# 7_ETH.net
KiCad netlist of a schematic drawn in Altium Designer
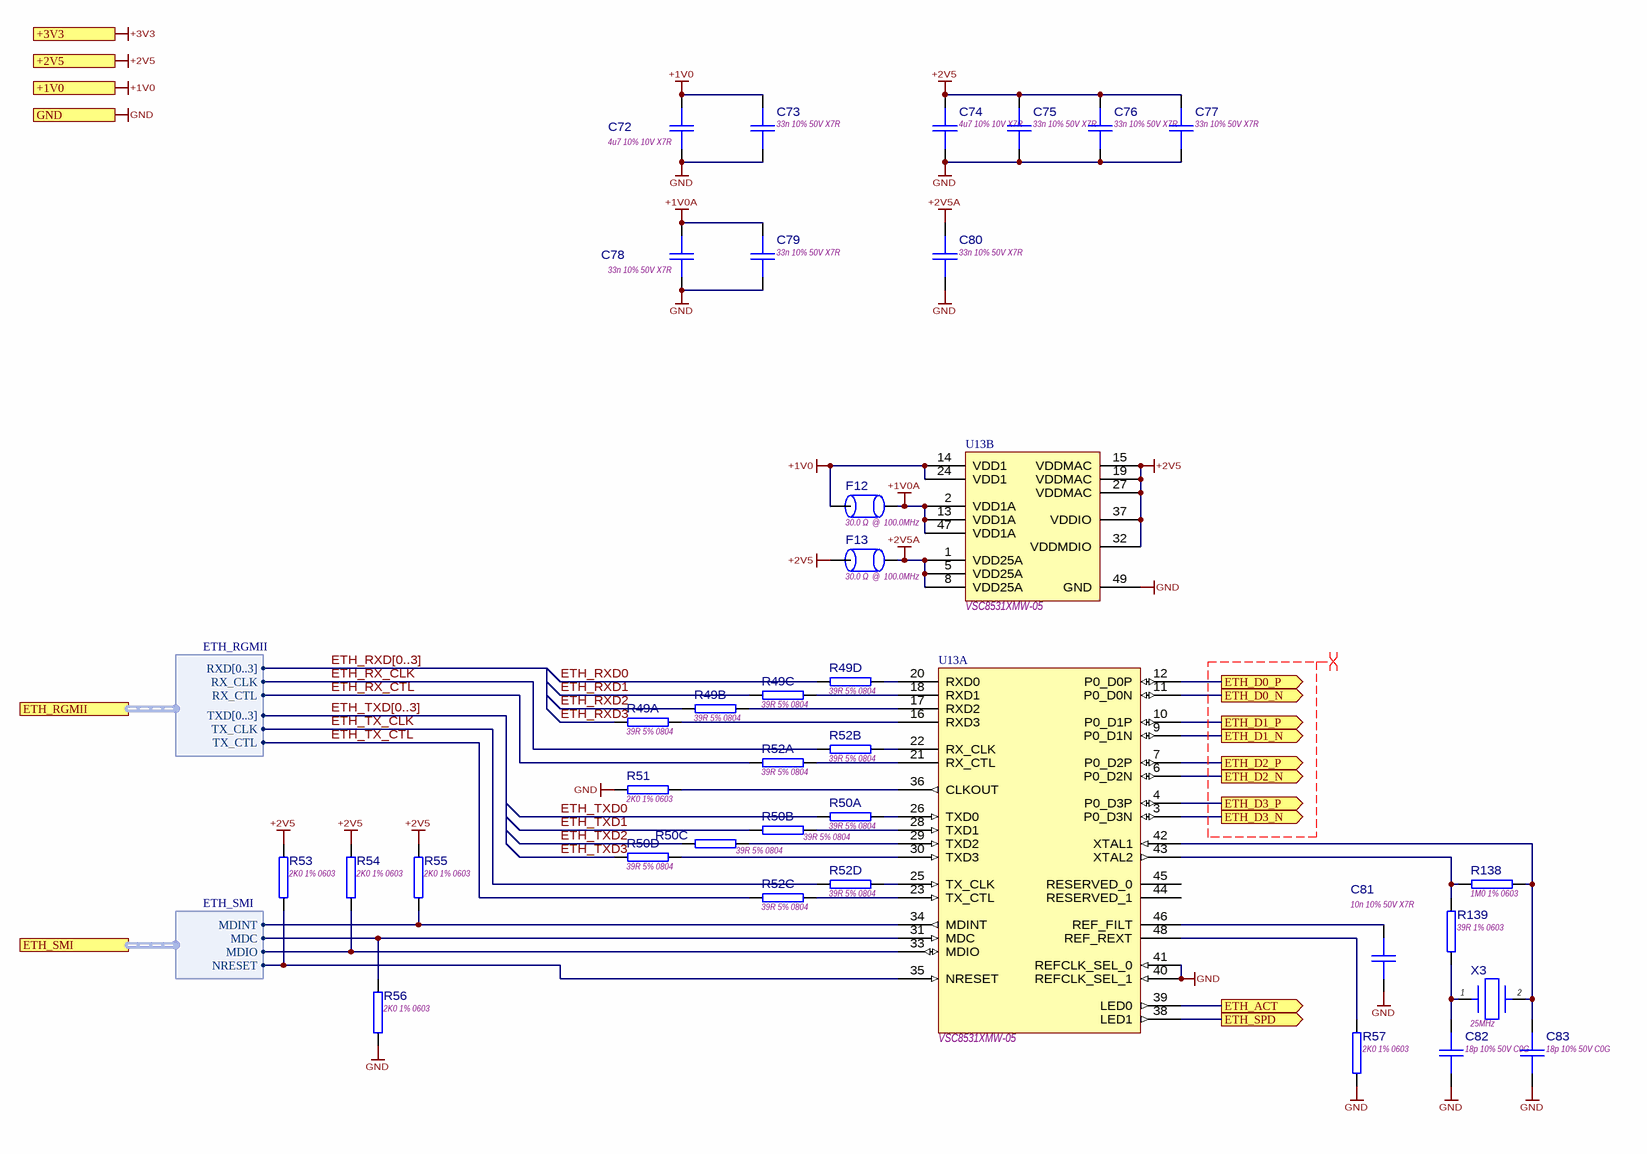
[diagram p0: [7] ETH.SchDoc]

(export (version "E")
  (design (tool "Eeschema 10.0.6"))
  (components
    (comp (ref "C72")
      (value "4u7 10% 10V X7R")
      (footprint "CAPC2012X145N")
      (description "Ceramic Chip Capacitor, 0805/2012")
      (fields (field (name "TOLERANCE") "10%"))
      (libsource (lib "Omnisys Vault") (part "CAP-2PIN"))
    )
    (comp (ref "C73")
      (value "33n 10% 50V X7R")
      (footprint "CAPC1005X55N")
      (description "Ceramic Chip Capacitor, 0402/1005")
      (fields (field (name "TOLERANCE") "10%"))
      (libsource (lib "Omnisys Vault") (part "CAP-2PIN"))
    )
    (comp (ref "C74")
      (value "4u7 10% 10V X7R")
      (footprint "CAPC2012X145N")
      (description "Ceramic Chip Capacitor, 0805/2012")
      (fields (field (name "TOLERANCE") "10%"))
      (libsource (lib "Omnisys Vault") (part "CAP-2PIN"))
    )
    (comp (ref "C75")
      (value "33n 10% 50V X7R")
      (footprint "CAPC1005X55N")
      (description "Ceramic Chip Capacitor, 0402/1005")
      (fields (field (name "TOLERANCE") "10%"))
      (libsource (lib "Omnisys Vault") (part "CAP-2PIN"))
    )
    (comp (ref "C76")
      (value "33n 10% 50V X7R")
      (footprint "CAPC1005X55N")
      (description "Ceramic Chip Capacitor, 0402/1005")
      (fields (field (name "TOLERANCE") "10%"))
      (libsource (lib "Omnisys Vault") (part "CAP-2PIN"))
    )
    (comp (ref "C77")
      (value "33n 10% 50V X7R")
      (footprint "CAPC1005X55N")
      (description "Ceramic Chip Capacitor, 0402/1005")
      (fields (field (name "TOLERANCE") "10%"))
      (libsource (lib "Omnisys Vault") (part "CAP-2PIN"))
    )
    (comp (ref "C78")
      (value "33n 10% 50V X7R")
      (footprint "CAPC1005X55N")
      (description "Ceramic Chip Capacitor, 0402/1005")
      (fields (field (name "TOLERANCE") "10%"))
      (libsource (lib "Omnisys Vault") (part "CAP-2PIN"))
    )
    (comp (ref "C79")
      (value "33n 10% 50V X7R")
      (footprint "CAPC1005X55N")
      (description "Ceramic Chip Capacitor, 0402/1005")
      (fields (field (name "TOLERANCE") "10%"))
      (libsource (lib "Omnisys Vault") (part "CAP-2PIN"))
    )
    (comp (ref "C80")
      (value "33n 10% 50V X7R")
      (footprint "CAPC1005X55N")
      (description "Ceramic Chip Capacitor, 0402/1005")
      (fields (field (name "TOLERANCE") "10%"))
      (libsource (lib "Omnisys Vault") (part "CAP-2PIN"))
    )
    (comp (ref "C81")
      (value "10n 10% 50V X7R")
      (footprint "CAPC1608X90N")
      (description "Ceramic Chip Capacitor, 0603/1608")
      (fields (field (name "TOLERANCE") "5%"))
      (libsource (lib "Omnisys Vault") (part "CAP-2PIN"))
    )
    (comp (ref "C82")
      (value "18p 10% 50V C0G")
      (footprint "CAPC1608X90N")
      (description "Ceramic Chip Capacitor, 0603/1608")
      (fields (field (name "TOLERANCE") "5%"))
      (libsource (lib "Omnisys Vault") (part "CAP-2PIN"))
    )
    (comp (ref "C83")
      (value "18p 10% 50V C0G")
      (footprint "CAPC1608X90N")
      (description "Ceramic Chip Capacitor, 0603/1608")
      (fields (field (name "TOLERANCE") "5%"))
      (libsource (lib "Omnisys Vault") (part "CAP-2PIN"))
    )
    (comp (ref "F12")
      (value "30.0 Ω  @  100.0MHz")
      (footprint "INDC2012X11L")
      (description "Ferrite bead, Würth Elektronik WE-CBF 2012 (0805), 74279206 ,  30.0 Ω  @  100.0MHz")
      (fields (field (name "PARTNUMBER") "74279206"))
      (libsource (lib "Omnisys Vault") (part "BEAD-2PIN"))
    )
    (comp (ref "F13")
      (value "30.0 Ω  @  100.0MHz")
      (footprint "INDC2012X11L")
      (description "Ferrite bead, Würth Elektronik WE-CBF 2012 (0805), 74279206 ,  30.0 Ω  @  100.0MHz")
      (fields (field (name "PARTNUMBER") "74279206"))
      (libsource (lib "Omnisys Vault") (part "BEAD-2PIN"))
    )
    (comp (ref "R49")
      (value "39R 5% 0804")
      (footprint "RESCAXS50P100X200X45-8N")
      (description "Thick film resistor array, 4 Resistors, Convex terminals, 0804/2010")
      (fields (field (name "TOLERANCE") "5%") (field (name "POWER") "62.5mW"))
      (libsource (lib "Omnisys Vault") (part "RES_ARRAY-8PIN"))
    )
    (comp (ref "R50")
      (value "39R 5% 0804")
      (footprint "RESCAXS50P100X200X45-8N")
      (description "Thick film resistor array, 4 Resistors, Convex terminals, 0804/2010")
      (fields (field (name "TOLERANCE") "5%") (field (name "POWER") "62.5mW"))
      (libsource (lib "Omnisys Vault") (part "RES_ARRAY-8PIN"))
    )
    (comp (ref "R51")
      (value "2K0 1% 0603")
      (footprint "RESC1608N")
      (description "Thick film Chip Resistor, 0603/1608")
      (fields (field (name "POWER") "100mW") (field (name "TOLERANCE") "1%"))
      (libsource (lib "Omnisys Vault") (part "RES-2PIN"))
    )
    (comp (ref "R52")
      (value "39R 5% 0804")
      (footprint "RESCAXS50P100X200X45-8N")
      (description "Thick film resistor array, 4 Resistors, Convex terminals, 0804/2010")
      (fields (field (name "TOLERANCE") "5%") (field (name "POWER") "62.5mW"))
      (libsource (lib "Omnisys Vault") (part "RES_ARRAY-8PIN"))
    )
    (comp (ref "R53")
      (value "2K0 1% 0603")
      (footprint "RESC1608N")
      (description "Thick film Chip Resistor, 0603/1608")
      (fields (field (name "POWER") "100mW") (field (name "TOLERANCE") "1%"))
      (libsource (lib "Omnisys Vault") (part "RES-2PIN"))
    )
    (comp (ref "R54")
      (value "2K0 1% 0603")
      (footprint "RESC1608N")
      (description "Thick film Chip Resistor, 0603/1608")
      (fields (field (name "POWER") "100mW") (field (name "TOLERANCE") "1%"))
      (libsource (lib "Omnisys Vault") (part "RES-2PIN"))
    )
    (comp (ref "R55")
      (value "2K0 1% 0603")
      (footprint "RESC1608N")
      (description "Thick film Chip Resistor, 0603/1608")
      (fields (field (name "POWER") "100mW") (field (name "TOLERANCE") "1%"))
      (libsource (lib "Omnisys Vault") (part "RES-2PIN"))
    )
    (comp (ref "R56")
      (value "2K0 1% 0603")
      (footprint "RESC1608N")
      (description "Thick film Chip Resistor, 0603/1608")
      (fields (field (name "POWER") "100mW") (field (name "TOLERANCE") "1%"))
      (libsource (lib "Omnisys Vault") (part "RES-2PIN"))
    )
    (comp (ref "R57")
      (value "2K0 1% 0603")
      (footprint "RESC1608N")
      (description "Thick film Chip Resistor, 0603/1608")
      (fields (field (name "POWER") "100mW") (field (name "TOLERANCE") "1%"))
      (libsource (lib "Omnisys Vault") (part "RES-2PIN"))
    )
    (comp (ref "R138")
      (value "1M0 1% 0603")
      (footprint "RESC1608L")
      (description "Thick film Chip Resistor, 0603/1608")
      (fields (field (name "POWER") "100mW") (field (name "TOLERANCE") "1%"))
      (libsource (lib "Omnisys Vault") (part "RES-2PIN"))
    )
    (comp (ref "R139")
      (value "39R 1% 0603")
      (footprint "RESC1608L")
      (description "Thick film Chip Resistor, 0603/1608")
      (fields (field (name "POWER") "100mW") (field (name "TOLERANCE") "1%"))
      (libsource (lib "Omnisys Vault") (part "RES-2PIN"))
    )
    (comp (ref "U13")
      (value "VSC8531XMW-05")
      (footprint "QFN40P600X600X90_HS-49N")
      (description "Single Port Gigabit Ethernet Copper PHY")
      (libsource (lib "Omnisys Vault") (part "VSC8531XMW-05"))
    )
    (comp (ref "X3")
      (value "25MHz")
      (footprint "XTAL_5x3.2MM")
      (description "25MHz 5 x 3.2 mm SMD GLASS CRYSTAL")
      (fields (field (name "PARTNUMBER") "7A-25.000MAHE-T"))
      (libsource (lib "Omnisys Vault") (part "XTAL-2PIN"))
    )
  )
  (nets
    (net (code "3") (name "+1V0") (class "Default")
      (node (ref "C72") (pin "2") (pinfunction "2_2") (pintype "passive"))
      (node (ref "C73") (pin "1") (pinfunction "1_1") (pintype "passive"))
      (node (ref "F12") (pin "1") (pinfunction "1_1") (pintype "passive"))
      (node (ref "U13") (pin "14") (pinfunction "VDD1_14") (pintype "power_in"))
      (node (ref "U13") (pin "24") (pinfunction "VDD1_24") (pintype "power_in"))
    )
    (net (code "4") (name "+1V0A") (class "Default")
      (node (ref "C78") (pin "1") (pinfunction "1_1") (pintype "passive"))
      (node (ref "C79") (pin "1") (pinfunction "1_1") (pintype "passive"))
      (node (ref "F12") (pin "2") (pinfunction "2_2") (pintype "passive"))
      (node (ref "U13") (pin "13") (pinfunction "VDD1A_13") (pintype "power_in"))
      (node (ref "U13") (pin "2") (pinfunction "VDD1A_2") (pintype "power_in"))
      (node (ref "U13") (pin "47") (pinfunction "VDD1A_47") (pintype "power_in"))
    )
    (net (code "5") (name "+2V5") (class "Default")
      (node (ref "C74") (pin "2") (pinfunction "2_2") (pintype "passive"))
      (node (ref "C75") (pin "1") (pinfunction "1_1") (pintype "passive"))
      (node (ref "C76") (pin "1") (pinfunction "1_1") (pintype "passive"))
      (node (ref "C77") (pin "1") (pinfunction "1_1") (pintype "passive"))
      (node (ref "F13") (pin "1") (pinfunction "1_1") (pintype "passive"))
      (node (ref "R53") (pin "2") (pinfunction "2_2") (pintype "passive"))
      (node (ref "R54") (pin "2") (pinfunction "2_2") (pintype "passive"))
      (node (ref "R55") (pin "2") (pinfunction "2_2") (pintype "passive"))
      (node (ref "U13") (pin "15") (pinfunction "VDDMAC_15") (pintype "power_in"))
      (node (ref "U13") (pin "19") (pinfunction "VDDMAC_19") (pintype "power_in"))
      (node (ref "U13") (pin "27") (pinfunction "VDDMAC_27") (pintype "power_in"))
      (node (ref "U13") (pin "32") (pinfunction "VDDMDIO_32") (pintype "power_in"))
      (node (ref "U13") (pin "37") (pinfunction "VDDIO_37") (pintype "power_in"))
    )
    (net (code "6") (name "+2V5A") (class "Default")
      (node (ref "C80") (pin "1") (pinfunction "1_1") (pintype "passive"))
      (node (ref "F13") (pin "2") (pinfunction "2_2") (pintype "passive"))
      (node (ref "U13") (pin "1") (pinfunction "VDD25A_1") (pintype "power_in"))
      (node (ref "U13") (pin "5") (pinfunction "VDD25A_5") (pintype "power_in"))
      (node (ref "U13") (pin "8") (pinfunction "VDD25A_8") (pintype "power_in"))
    )
    (net (code "8") (name "/ETH_ACT") (class "Default")
      (node (ref "U13") (pin "39") (pinfunction "LED0_39") (pintype "output"))
    )
    (net (code "9") (name "/ETH_D0_N") (class "Default")
      (node (ref "U13") (pin "11") (pinfunction "P0_D0N_11") (pintype "bidirectional"))
    )
    (net (code "10") (name "/ETH_D0_P") (class "Default")
      (node (ref "U13") (pin "12") (pinfunction "P0_D0P_12") (pintype "bidirectional"))
    )
    (net (code "11") (name "/ETH_D1_N") (class "Default")
      (node (ref "U13") (pin "9") (pinfunction "P0_D1N_9") (pintype "bidirectional"))
    )
    (net (code "12") (name "/ETH_D1_P") (class "Default")
      (node (ref "U13") (pin "10") (pinfunction "P0_D1P_10") (pintype "bidirectional"))
    )
    (net (code "13") (name "/ETH_D2_N") (class "Default")
      (node (ref "U13") (pin "6") (pinfunction "P0_D2N_6") (pintype "bidirectional"))
    )
    (net (code "14") (name "/ETH_D2_P") (class "Default")
      (node (ref "U13") (pin "7") (pinfunction "P0_D2P_7") (pintype "bidirectional"))
    )
    (net (code "15") (name "/ETH_D3_N") (class "Default")
      (node (ref "U13") (pin "3") (pinfunction "P0_D3N_3") (pintype "bidirectional"))
    )
    (net (code "16") (name "/ETH_D3_P") (class "Default")
      (node (ref "U13") (pin "4") (pinfunction "P0_D3P_4") (pintype "bidirectional"))
    )
    (net (code "18") (name "/ETH_RXD0") (class "Default") (node (ref "R49") (pin "4") (pintype "passive")))
    (net (code "19") (name "/ETH_RXD1") (class "Default") (node (ref "R49") (pin "3") (pintype "passive")))
    (net (code "20") (name "/ETH_RXD2") (class "Default") (node (ref "R49") (pin "2") (pintype "passive")))
    (net (code "21") (name "/ETH_RXD3") (class "Default") (node (ref "R49") (pin "1") (pintype "passive")))
    (net (code "22") (name "/ETH_RX_CLK") (class "Default") (node (ref "R52") (pin "2") (pintype "passive")))
    (net (code "23") (name "/ETH_RX_CTL") (class "Default") (node (ref "R52") (pin "1") (pintype "passive")))
    (net (code "24") (name "/ETH_SPD") (class "Default")
      (node (ref "U13") (pin "38") (pinfunction "LED1_38") (pintype "output"))
    )
    (net (code "25") (name "/ETH_TXD0") (class "Default") (node (ref "R50") (pin "1") (pintype "passive")))
    (net (code "26") (name "/ETH_TXD1") (class "Default") (node (ref "R50") (pin "2") (pintype "passive")))
    (net (code "27") (name "/ETH_TXD2") (class "Default") (node (ref "R50") (pin "3") (pintype "passive")))
    (net (code "28") (name "/ETH_TXD3") (class "Default") (node (ref "R50") (pin "4") (pintype "passive")))
    (net (code "30") (name "/ETH_TX_CLK") (class "Default") (node (ref "R52") (pin "4") (pintype "passive")))
    (net (code "31") (name "/ETH_TX_CTL") (class "Default") (node (ref "R52") (pin "3") (pintype "passive")))
    (net (code "34") (name "GND") (class "Default")
      (node (ref "C72") (pin "1") (pinfunction "1_1") (pintype "passive"))
      (node (ref "C73") (pin "2") (pinfunction "2_2") (pintype "passive"))
      (node (ref "C74") (pin "1") (pinfunction "1_1") (pintype "passive"))
      (node (ref "C75") (pin "2") (pinfunction "2_2") (pintype "passive"))
      (node (ref "C76") (pin "2") (pinfunction "2_2") (pintype "passive"))
      (node (ref "C77") (pin "2") (pinfunction "2_2") (pintype "passive"))
      (node (ref "C78") (pin "2") (pinfunction "2_2") (pintype "passive"))
      (node (ref "C79") (pin "2") (pinfunction "2_2") (pintype "passive"))
      (node (ref "C80") (pin "2") (pinfunction "2_2") (pintype "passive"))
      (node (ref "C81") (pin "2") (pinfunction "2_2") (pintype "passive"))
      (node (ref "C82") (pin "1") (pinfunction "1_1") (pintype "passive"))
      (node (ref "C83") (pin "1") (pinfunction "1_1") (pintype "passive"))
      (node (ref "R51") (pin "2") (pinfunction "2_2") (pintype "passive"))
      (node (ref "R56") (pin "1") (pinfunction "1_1") (pintype "passive"))
      (node (ref "R57") (pin "1") (pinfunction "1_1") (pintype "passive"))
      (node (ref "U13") (pin "40") (pinfunction "REFCLK_SEL_1_40") (pintype "input"))
      (node (ref "U13") (pin "41") (pinfunction "REFCLK_SEL_0_41") (pintype "input"))
      (node (ref "U13") (pin "49") (pinfunction "GND_49") (pintype "power_in"))
    )
    (net (code "35") (name "Net-(C82-Pad2)") (class "Default")
      (node (ref "C82") (pin "2") (pinfunction "2_2") (pintype "passive"))
      (node (ref "R139") (pin "2") (pinfunction "2_2") (pintype "passive"))
      (node (ref "X3") (pin "1") (pinfunction "1_1") (pintype "passive"))
    )
    (net (code "36") (name "Net-(U13A-CLKOUT)") (class "Default")
      (node (ref "R51") (pin "1") (pinfunction "1_1") (pintype "passive"))
      (node (ref "U13") (pin "36") (pinfunction "CLKOUT_36") (pintype "output"))
    )
    (net (code "37") (name "Net-(U13A-MDC)") (class "Default")
      (node (ref "R56") (pin "2") (pinfunction "2_2") (pintype "passive"))
      (node (ref "U13") (pin "31") (pinfunction "MDC_31") (pintype "input"))
    )
    (net (code "38") (name "Net-(U13A-MDINT)") (class "Default")
      (node (ref "R55") (pin "1") (pinfunction "1_1") (pintype "passive"))
      (node (ref "U13") (pin "34") (pinfunction "MDINT_34") (pintype "output"))
    )
    (net (code "39") (name "Net-(U13A-MDIO)") (class "Default")
      (node (ref "R54") (pin "1") (pinfunction "1_1") (pintype "passive"))
      (node (ref "U13") (pin "33") (pinfunction "MDIO_33") (pintype "bidirectional"))
    )
    (net (code "40") (name "Net-(U13A-NRESET)") (class "Default")
      (node (ref "R53") (pin "1") (pinfunction "1_1") (pintype "passive"))
      (node (ref "U13") (pin "35") (pinfunction "NRESET_35") (pintype "input"))
    )
    (net (code "41") (name "Net-(U13A-REF_FILT)") (class "Default")
      (node (ref "C81") (pin "1") (pinfunction "1_1") (pintype "passive"))
      (node (ref "U13") (pin "46") (pinfunction "REF_FILT_46") (pintype "power_in"))
    )
    (net (code "42") (name "Net-(U13A-REF_REXT)") (class "Default")
      (node (ref "R57") (pin "2") (pinfunction "2_2") (pintype "passive"))
      (node (ref "U13") (pin "48") (pinfunction "REF_REXT_48") (pintype "power_in"))
    )
    (net (code "43") (name "Net-(U13A-RXD0)") (class "Default")
      (node (ref "R49") (pin "5") (pintype "passive"))
      (node (ref "U13") (pin "20") (pinfunction "RXD0_20") (pintype "passive"))
    )
    (net (code "44") (name "Net-(U13A-RXD1)") (class "Default")
      (node (ref "R49") (pin "6") (pintype "passive"))
      (node (ref "U13") (pin "18") (pinfunction "RXD1_18") (pintype "passive"))
    )
    (net (code "45") (name "Net-(U13A-RXD2)") (class "Default")
      (node (ref "R49") (pin "7") (pintype "passive"))
      (node (ref "U13") (pin "17") (pinfunction "RXD2_17") (pintype "passive"))
    )
    (net (code "46") (name "Net-(U13A-RXD3)") (class "Default")
      (node (ref "R49") (pin "8") (pintype "passive"))
      (node (ref "U13") (pin "16") (pinfunction "RXD3_16") (pintype "passive"))
    )
    (net (code "47") (name "Net-(U13A-RX_CLK)") (class "Default")
      (node (ref "R52") (pin "7") (pintype "passive"))
      (node (ref "U13") (pin "22") (pinfunction "RX_CLK_22") (pintype "passive"))
    )
    (net (code "48") (name "Net-(U13A-RX_CTL)") (class "Default")
      (node (ref "R52") (pin "8") (pintype "passive"))
      (node (ref "U13") (pin "21") (pinfunction "RX_CTL_21") (pintype "passive"))
    )
    (net (code "49") (name "Net-(U13A-TXD0)") (class "Default")
      (node (ref "R50") (pin "8") (pintype "passive"))
      (node (ref "U13") (pin "26") (pinfunction "TXD0_26") (pintype "input"))
    )
    (net (code "50") (name "Net-(U13A-TXD1)") (class "Default")
      (node (ref "R50") (pin "7") (pintype "passive"))
      (node (ref "U13") (pin "28") (pinfunction "TXD1_28") (pintype "input"))
    )
    (net (code "51") (name "Net-(U13A-TXD2)") (class "Default")
      (node (ref "R50") (pin "6") (pintype "passive"))
      (node (ref "U13") (pin "29") (pinfunction "TXD2_29") (pintype "input"))
    )
    (net (code "52") (name "Net-(U13A-TXD3)") (class "Default")
      (node (ref "R50") (pin "5") (pintype "passive"))
      (node (ref "U13") (pin "30") (pinfunction "TXD3_30") (pintype "input"))
    )
    (net (code "53") (name "Net-(U13A-TX_CLK)") (class "Default")
      (node (ref "R52") (pin "5") (pintype "passive"))
      (node (ref "U13") (pin "25") (pinfunction "TX_CLK_25") (pintype "input"))
    )
    (net (code "54") (name "Net-(U13A-TX_CTL)") (class "Default")
      (node (ref "R52") (pin "6") (pintype "passive"))
      (node (ref "U13") (pin "23") (pinfunction "TX_CTL_23") (pintype "input"))
    )
    (net (code "55") (name "Net-(U13A-XTAL1)") (class "Default")
      (node (ref "C83") (pin "2") (pinfunction "2_2") (pintype "passive"))
      (node (ref "R138") (pin "2") (pinfunction "2_2") (pintype "passive"))
      (node (ref "U13") (pin "42") (pinfunction "XTAL1_42") (pintype "input"))
      (node (ref "X3") (pin "2") (pinfunction "2_2") (pintype "passive"))
    )
    (net (code "56") (name "Net-(U13A-XTAL2)") (class "Default")
      (node (ref "R138") (pin "1") (pinfunction "1_1") (pintype "passive"))
      (node (ref "R139") (pin "1") (pinfunction "1_1") (pintype "passive"))
      (node (ref "U13") (pin "43") (pinfunction "XTAL2_43") (pintype "output"))
    )
    (net (code "57") (name "unconnected-(U13A-RESERVED_0-Pad45)") (class "Default")
      (node (ref "U13") (pin "45") (pinfunction "RESERVED_0_45") (pintype "passive"))
    )
    (net (code "58") (name "unconnected-(U13A-RESERVED_1-Pad44)") (class "Default")
      (node (ref "U13") (pin "44") (pinfunction "RESERVED_1_44") (pintype "passive"))
    )
  )
)
